# LedSymbols.net
KiCad netlist of a schematic drawn in EAGLE
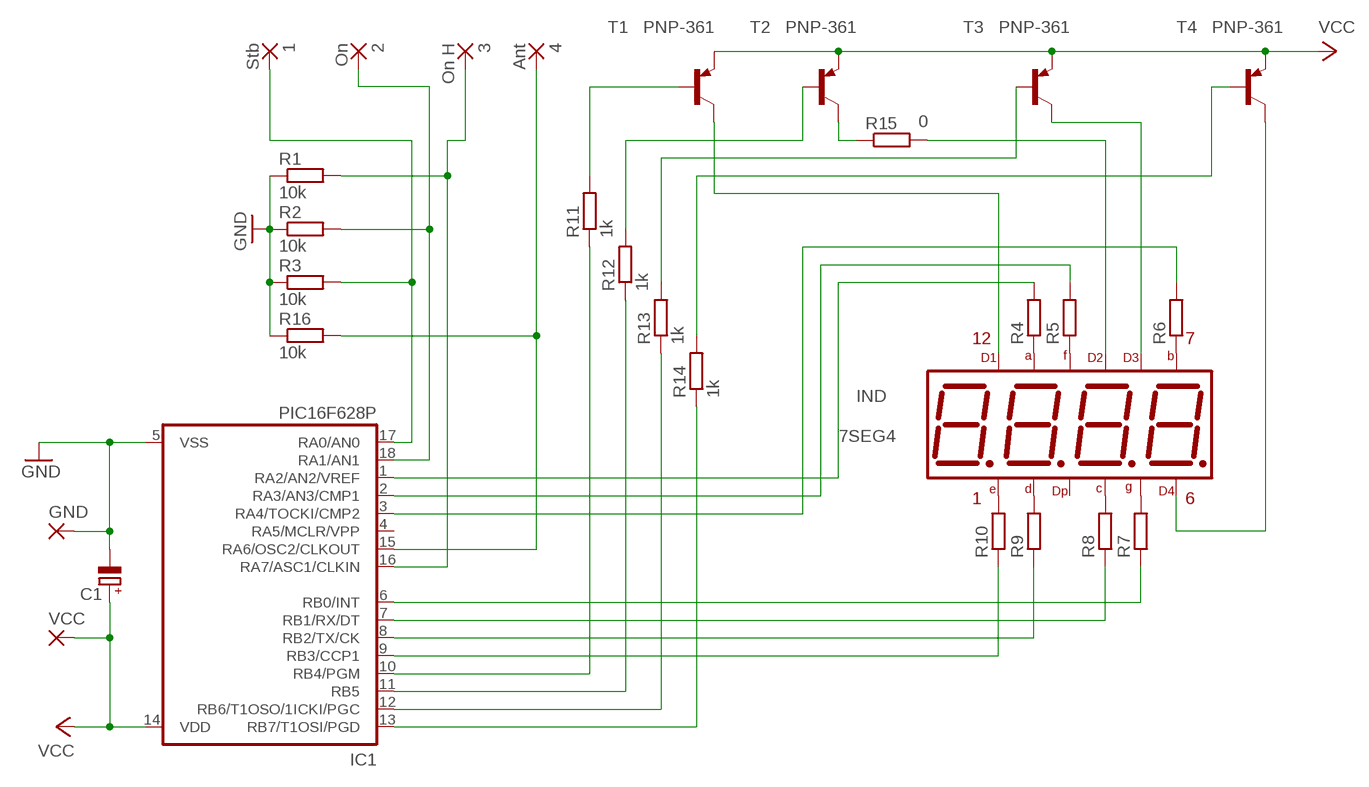
[diagram p0: schematic, sheet 1]

(export (version "E")
  (design (tool "Eeschema 10.0.6"))
  (components
    (comp (ref "1")
      (value "Stb")
      (footprint "eagle-import:1,6_0,8")
      (libsource (lib "eagle-import") (part "1,6/0,8"))
    )
    (comp (ref "2")
      (value "On")
      (footprint "eagle-import:1,6_0,8")
      (libsource (lib "eagle-import") (part "1,6/0,8"))
    )
    (comp (ref "3")
      (value "On H")
      (footprint "eagle-import:1,6_0,8")
      (libsource (lib "eagle-import") (part "1,6/0,8"))
    )
    (comp (ref "4")
      (value "Ant")
      (footprint "eagle-import:1,6_0,8")
      (libsource (lib "eagle-import") (part "1,6/0,8"))
    )
    (comp (ref "C1")
      (value "CPOL-EUSMCC")
      (footprint "eagle-import:SMC_C")
      (libsource (lib "eagle-import") (part "CPOL-EUSMCC"))
    )
    (comp (ref "GND")
      (value "2,15/1,0")
      (footprint "eagle-import:2,15_1,0")
      (libsource (lib "eagle-import") (part "2,15/1,0"))
    )
    (comp (ref "IC1")
      (value "PIC16F628P")
      (footprint "eagle-import:DIL18")
      (fields (field (name "MF") "MICROCHIP") (field (name "MPN") "PIC16F628-20/P"))
      (libsource (lib "eagle-import") (part "PIC16F628P"))
    )
    (comp (ref "IND")
      (value "7SEG4")
      (footprint "eagle-import:7SEG4")
      (libsource (lib "eagle-import") (part "7SEG4"))
    )
    (comp (ref "R1")
      (value "10k")
      (footprint "eagle-import:M0805")
      (libsource (lib "eagle-import") (part "R-EU_M0805"))
    )
    (comp (ref "R2")
      (value "10k")
      (footprint "eagle-import:M0805")
      (libsource (lib "eagle-import") (part "R-EU_M0805"))
    )
    (comp (ref "R3")
      (value "10k")
      (footprint "eagle-import:M0805")
      (libsource (lib "eagle-import") (part "R-EU_M0805"))
    )
    (comp (ref "R4")
      (value "R-EU_M0805")
      (footprint "eagle-import:M0805")
      (libsource (lib "eagle-import") (part "R-EU_M0805"))
    )
    (comp (ref "R5")
      (value "R-EU_M0805")
      (footprint "eagle-import:M0805")
      (libsource (lib "eagle-import") (part "R-EU_M0805"))
    )
    (comp (ref "R6")
      (value "R-EU_M0805")
      (footprint "eagle-import:M0805")
      (libsource (lib "eagle-import") (part "R-EU_M0805"))
    )
    (comp (ref "R7")
      (value "R-EU_M0805")
      (footprint "eagle-import:M0805")
      (libsource (lib "eagle-import") (part "R-EU_M0805"))
    )
    (comp (ref "R8")
      (value "R-EU_M0805")
      (footprint "eagle-import:M0805")
      (libsource (lib "eagle-import") (part "R-EU_M0805"))
    )
    (comp (ref "R9")
      (value "R-EU_M0805")
      (footprint "eagle-import:M0805")
      (libsource (lib "eagle-import") (part "R-EU_M0805"))
    )
    (comp (ref "R10")
      (value "R-EU_M0805")
      (footprint "eagle-import:M0805")
      (libsource (lib "eagle-import") (part "R-EU_M0805"))
    )
    (comp (ref "R11")
      (value "1k")
      (footprint "eagle-import:M0805")
      (libsource (lib "eagle-import") (part "R-EU_M0805"))
    )
    (comp (ref "R12")
      (value "1k")
      (footprint "eagle-import:M0805")
      (libsource (lib "eagle-import") (part "R-EU_M0805"))
    )
    (comp (ref "R13")
      (value "1k")
      (footprint "eagle-import:M0805")
      (libsource (lib "eagle-import") (part "R-EU_M0805"))
    )
    (comp (ref "R14")
      (value "1k")
      (footprint "eagle-import:M0805")
      (libsource (lib "eagle-import") (part "R-EU_M0805"))
    )
    (comp (ref "R15")
      (value "0")
      (footprint "eagle-import:M1206")
      (libsource (lib "eagle-import") (part "R-EU_M1206"))
    )
    (comp (ref "R16")
      (value "10k")
      (footprint "eagle-import:M0805")
      (libsource (lib "eagle-import") (part "R-EU_M0805"))
    )
    (comp (ref "T1")
      (value "PNP-361")
      (footprint "eagle-import:PNP-361")
      (libsource (lib "eagle-import") (part "PNP-361"))
    )
    (comp (ref "T2")
      (value "PNP-361")
      (footprint "eagle-import:PNP-361")
      (libsource (lib "eagle-import") (part "PNP-361"))
    )
    (comp (ref "T3")
      (value "PNP-361")
      (footprint "eagle-import:PNP-361")
      (libsource (lib "eagle-import") (part "PNP-361"))
    )
    (comp (ref "T4")
      (value "PNP-361")
      (footprint "eagle-import:PNP-361")
      (libsource (lib "eagle-import") (part "PNP-361"))
    )
    (comp (ref "VCC")
      (value "2,15/1,0")
      (footprint "eagle-import:2,15_1,0")
      (libsource (lib "eagle-import") (part "2,15/1,0"))
    )
  )
  (nets
    (net (code "1") (name "GND") (class "Default")
      (node (ref "C1") (pin "-") (pinfunction "-_-") (pintype "passive"))
      (node (ref "GND") (pin "1") (pinfunction "P_1") (pintype "passive"))
      (node (ref "IC1") (pin "5") (pinfunction "VSS_5") (pintype "power_in"))
      (node (ref "R1") (pin "1") (pinfunction "1_1") (pintype "passive"))
      (node (ref "R16") (pin "1") (pinfunction "1_1") (pintype "passive"))
      (node (ref "R2") (pin "1") (pinfunction "1_1") (pintype "passive"))
      (node (ref "R3") (pin "1") (pinfunction "1_1") (pintype "passive"))
    )
    (net (code "2") (name "Net-(1-P)") (class "Default")
      (node (ref "1") (pin "1") (pinfunction "P_1") (pintype "passive"))
      (node (ref "IC1") (pin "17") (pinfunction "RA0/AN0_17") (pintype "bidirectional"))
      (node (ref "R3") (pin "2") (pinfunction "2_2") (pintype "passive"))
    )
    (net (code "3") (name "Net-(2-P)") (class "Default")
      (node (ref "2") (pin "1") (pinfunction "P_1") (pintype "passive"))
      (node (ref "IC1") (pin "18") (pinfunction "RA1/AN1_18") (pintype "bidirectional"))
      (node (ref "R2") (pin "2") (pinfunction "2_2") (pintype "passive"))
    )
    (net (code "4") (name "Net-(3-P)") (class "Default")
      (node (ref "3") (pin "1") (pinfunction "P_1") (pintype "passive"))
      (node (ref "IC1") (pin "16") (pinfunction "RA7/ASC1/CLKIN_16") (pintype "bidirectional"))
      (node (ref "R1") (pin "2") (pinfunction "2_2") (pintype "passive"))
    )
    (net (code "5") (name "Net-(4-P)") (class "Default")
      (node (ref "4") (pin "1") (pinfunction "P_1") (pintype "passive"))
      (node (ref "IC1") (pin "15") (pinfunction "RA6/OSC2/CLKOUT_15") (pintype "bidirectional"))
      (node (ref "R16") (pin "2") (pinfunction "2_2") (pintype "passive"))
    )
    (net (code "6") (name "Net-(IC1-RA2{slash}AN2{slash}VREF)") (class "Default")
      (node (ref "IC1") (pin "1") (pinfunction "RA2/AN2/VREF_1") (pintype "bidirectional"))
      (node (ref "R4") (pin "2") (pinfunction "2_2") (pintype "passive"))
    )
    (net (code "7") (name "Net-(IC1-RA3{slash}AN3{slash}CMP1)") (class "Default")
      (node (ref "IC1") (pin "2") (pinfunction "RA3/AN3/CMP1_2") (pintype "bidirectional"))
      (node (ref "R5") (pin "2") (pinfunction "2_2") (pintype "passive"))
    )
    (net (code "8") (name "Net-(IC1-RA4{slash}TOCKI{slash}CMP2)") (class "Default")
      (node (ref "IC1") (pin "3") (pinfunction "RA4/TOCKI/CMP2_3") (pintype "bidirectional"))
      (node (ref "R6") (pin "2") (pinfunction "2_2") (pintype "passive"))
    )
    (net (code "9") (name "Net-(IC1-RB0{slash}INT)") (class "Default")
      (node (ref "IC1") (pin "6") (pinfunction "RB0/INT_6") (pintype "bidirectional"))
      (node (ref "R7") (pin "1") (pinfunction "1_1") (pintype "passive"))
    )
    (net (code "10") (name "Net-(IC1-RB1{slash}RX{slash}DT)") (class "Default")
      (node (ref "IC1") (pin "7") (pinfunction "RB1/RX/DT_7") (pintype "bidirectional"))
      (node (ref "R8") (pin "1") (pinfunction "1_1") (pintype "passive"))
    )
    (net (code "11") (name "Net-(IC1-RB2{slash}TX{slash}CK)") (class "Default")
      (node (ref "IC1") (pin "8") (pinfunction "RB2/TX/CK_8") (pintype "bidirectional"))
      (node (ref "R9") (pin "1") (pinfunction "1_1") (pintype "passive"))
    )
    (net (code "12") (name "Net-(IC1-RB3{slash}CCP1)") (class "Default")
      (node (ref "IC1") (pin "9") (pinfunction "RB3/CCP1_9") (pintype "bidirectional"))
      (node (ref "R10") (pin "1") (pinfunction "1_1") (pintype "passive"))
    )
    (net (code "13") (name "Net-(IC1-RB4{slash}PGM)") (class "Default")
      (node (ref "IC1") (pin "10") (pinfunction "RB4/PGM_10") (pintype "bidirectional"))
      (node (ref "R11") (pin "1") (pinfunction "1_1") (pintype "passive"))
    )
    (net (code "14") (name "Net-(IC1-RB5)") (class "Default")
      (node (ref "IC1") (pin "11") (pinfunction "RB5_11") (pintype "bidirectional"))
      (node (ref "R12") (pin "1") (pinfunction "1_1") (pintype "passive"))
    )
    (net (code "15") (name "Net-(IC1-RB6{slash}T1OSO{slash}1ICKI{slash}PGC)") (class "Default")
      (node (ref "IC1") (pin "12") (pinfunction "RB6/T1OSO/1ICKI/PGC_12") (pintype "bidirectional"))
      (node (ref "R13") (pin "1") (pinfunction "1_1") (pintype "passive"))
    )
    (net (code "16") (name "Net-(IC1-RB7{slash}T1OSI{slash}PGD)") (class "Default")
      (node (ref "IC1") (pin "13") (pinfunction "RB7/T1OSI/PGD_13") (pintype "bidirectional"))
      (node (ref "R14") (pin "1") (pinfunction "1_1") (pintype "passive"))
    )
    (net (code "17") (name "Net-(IND-PadA)") (class "Default")
      (node (ref "IND") (pin "A") (pinfunction "A_A") (pintype "passive"))
      (node (ref "R4") (pin "1") (pinfunction "1_1") (pintype "passive"))
    )
    (net (code "18") (name "Net-(IND-PadB)") (class "Default")
      (node (ref "IND") (pin "B") (pinfunction "B_B") (pintype "passive"))
      (node (ref "R6") (pin "1") (pinfunction "1_1") (pintype "passive"))
    )
    (net (code "19") (name "Net-(IND-PadC)") (class "Default")
      (node (ref "IND") (pin "C") (pinfunction "C_C") (pintype "passive"))
      (node (ref "R8") (pin "2") (pinfunction "2_2") (pintype "passive"))
    )
    (net (code "20") (name "Net-(IND-PadD)") (class "Default")
      (node (ref "IND") (pin "D") (pinfunction "D_D") (pintype "passive"))
      (node (ref "R9") (pin "2") (pinfunction "2_2") (pintype "passive"))
    )
    (net (code "21") (name "Net-(IND-PadD1)") (class "Default")
      (node (ref "IND") (pin "D1") (pinfunction "D1_D1") (pintype "passive"))
      (node (ref "T1") (pin "C") (pinfunction "C_C") (pintype "passive"))
    )
    (net (code "22") (name "Net-(IND-PadD2)") (class "Default")
      (node (ref "IND") (pin "D2") (pinfunction "D2_D2") (pintype "passive"))
      (node (ref "R15") (pin "2") (pinfunction "2_2") (pintype "passive"))
    )
    (net (code "23") (name "Net-(IND-PadD3)") (class "Default")
      (node (ref "IND") (pin "D3") (pinfunction "D3_D3") (pintype "passive"))
      (node (ref "T3") (pin "C") (pinfunction "C_C") (pintype "passive"))
    )
    (net (code "24") (name "Net-(IND-PadD4)") (class "Default")
      (node (ref "IND") (pin "D4") (pinfunction "D4_D4") (pintype "passive"))
      (node (ref "T4") (pin "C") (pinfunction "C_C") (pintype "passive"))
    )
    (net (code "25") (name "Net-(IND-PadE)") (class "Default")
      (node (ref "IND") (pin "E") (pinfunction "E_E") (pintype "passive"))
      (node (ref "R10") (pin "2") (pinfunction "2_2") (pintype "passive"))
    )
    (net (code "26") (name "Net-(IND-PadF)") (class "Default")
      (node (ref "IND") (pin "F") (pinfunction "F_F") (pintype "passive"))
      (node (ref "R5") (pin "1") (pinfunction "1_1") (pintype "passive"))
    )
    (net (code "27") (name "Net-(IND-PadG)") (class "Default")
      (node (ref "IND") (pin "G") (pinfunction "G_G") (pintype "passive"))
      (node (ref "R7") (pin "2") (pinfunction "2_2") (pintype "passive"))
    )
    (net (code "28") (name "Net-(R11-Pad2)") (class "Default")
      (node (ref "R11") (pin "2") (pinfunction "2_2") (pintype "passive"))
      (node (ref "T1") (pin "B") (pinfunction "B_B") (pintype "passive"))
    )
    (net (code "29") (name "Net-(R12-Pad2)") (class "Default")
      (node (ref "R12") (pin "2") (pinfunction "2_2") (pintype "passive"))
      (node (ref "T2") (pin "B") (pinfunction "B_B") (pintype "passive"))
    )
    (net (code "30") (name "Net-(R13-Pad2)") (class "Default")
      (node (ref "R13") (pin "2") (pinfunction "2_2") (pintype "passive"))
      (node (ref "T3") (pin "B") (pinfunction "B_B") (pintype "passive"))
    )
    (net (code "31") (name "Net-(R14-Pad2)") (class "Default")
      (node (ref "R14") (pin "2") (pinfunction "2_2") (pintype "passive"))
      (node (ref "T4") (pin "B") (pinfunction "B_B") (pintype "passive"))
    )
    (net (code "32") (name "Net-(R15-Pad1)") (class "Default")
      (node (ref "R15") (pin "1") (pinfunction "1_1") (pintype "passive"))
      (node (ref "T2") (pin "C") (pinfunction "C_C") (pintype "passive"))
    )
    (net (code "33") (name "VCC") (class "Default")
      (node (ref "C1") (pin "+") (pinfunction "+_+") (pintype "passive"))
      (node (ref "IC1") (pin "14") (pinfunction "VDD_14") (pintype "power_in"))
      (node (ref "T1") (pin "E") (pinfunction "E_E") (pintype "passive"))
      (node (ref "T2") (pin "E") (pinfunction "E_E") (pintype "passive"))
      (node (ref "T3") (pin "E") (pinfunction "E_E") (pintype "passive"))
      (node (ref "T4") (pin "E") (pinfunction "E_E") (pintype "passive"))
      (node (ref "VCC") (pin "1") (pinfunction "P_1") (pintype "passive"))
    )
    (net (code "34") (name "unconnected-(IC1-RA5{slash}MCLR{slash}VPP-Pad4)") (class "Default")
      (node (ref "IC1") (pin "4") (pinfunction "RA5/MCLR/VPP_4") (pintype "input"))
    )
    (net (code "35") (name "unconnected-(IND-PadDP)") (class "Default")
      (node (ref "IND") (pin "DP") (pinfunction "DP_DP") (pintype "passive"))
    )
  )
)
